# Main_PCB.net
KiCad netlist of a schematic drawn in Altium Designer
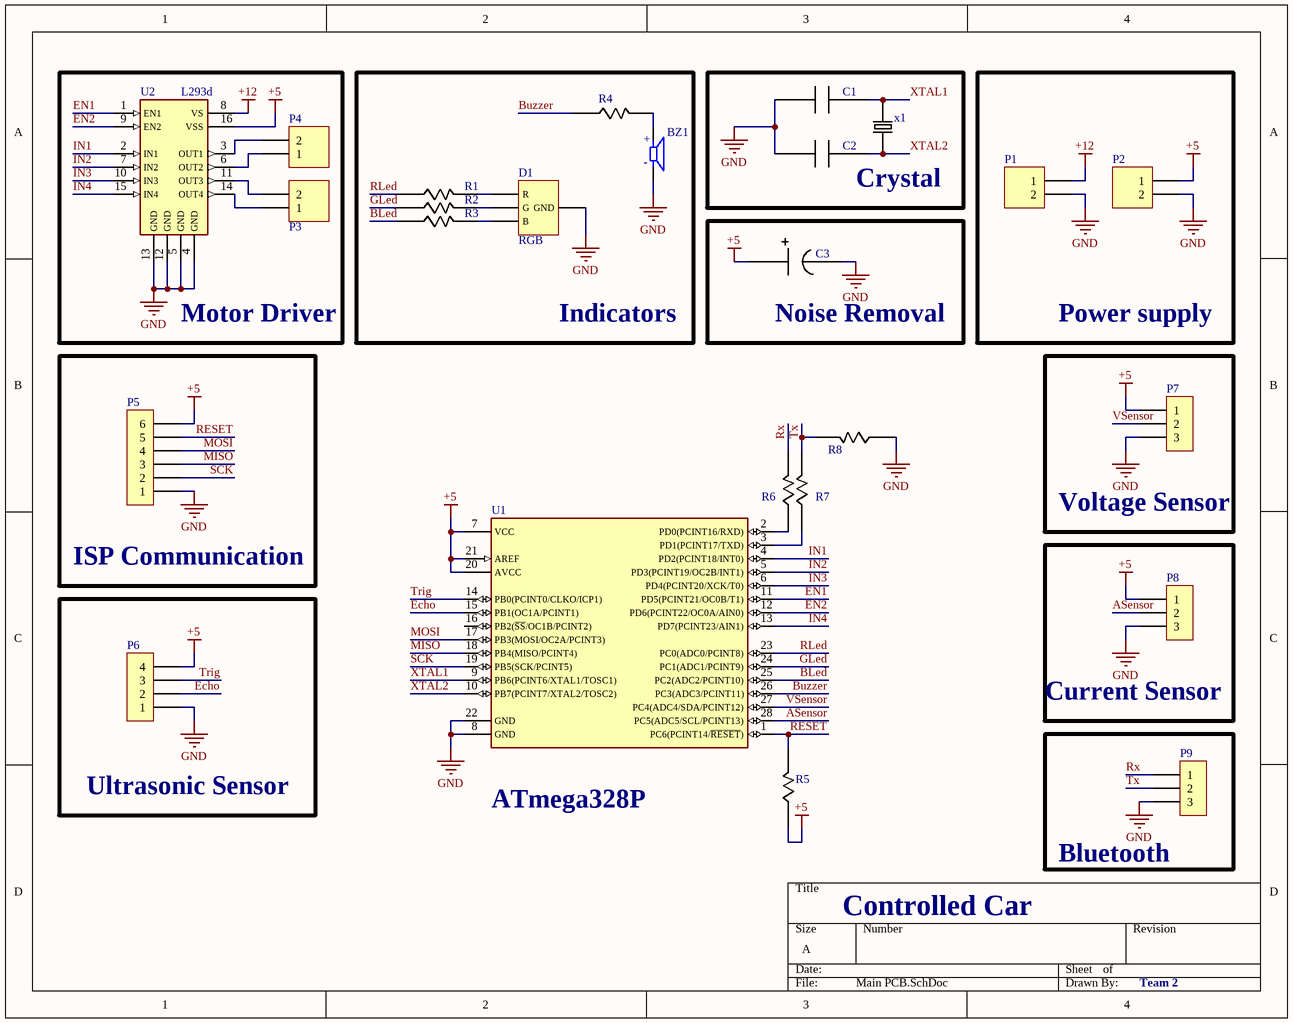
[diagram p0: Main PCB.SchDoc]

(export (version "E")
  (design (tool "Eeschema 10.0.6"))
  (components
    (comp (ref "BZ1") (value "BUZZER") (footprint "BUZZER") (libsource (lib "Schlib1") (part "BUZZER")))
    (comp (ref "C1")
      (value "Capacitor")
      (footprint "CAPACITOR")
      (libsource (lib "Schlib1") (part "Capacitor"))
    )
    (comp (ref "C2")
      (value "Capacitor")
      (footprint "CAPACITOR")
      (libsource (lib "Schlib1") (part "Capacitor"))
    )
    (comp (ref "C3")
      (value "Polarized cap")
      (footprint "POL CAP")
      (libsource (lib "Schlib1") (part "Polarized cap"))
    )
    (comp (ref "D1") (value "RGB") (footprint "RGB") (libsource (lib "Schlib1") (part "RGB")))
    (comp (ref "P1")
      (value "Terminal block")
      (footprint "TERMINAL BLOCK")
      (libsource (lib "Schlib1") (part "Terminal block"))
    )
    (comp (ref "P2")
      (value "Terminal block")
      (footprint "TERMINAL BLOCK")
      (libsource (lib "Schlib1") (part "Terminal block"))
    )
    (comp (ref "P3")
      (value "Terminal block")
      (footprint "TERMINAL BLOCK")
      (libsource (lib "") (part "Terminal block_1"))
    )
    (comp (ref "P4")
      (value "Terminal block")
      (footprint "TERMINAL BLOCK")
      (libsource (lib "") (part "Terminal block_1"))
    )
    (comp (ref "P5")
      (value "6 pins")
      (footprint "6 Pins connector")
      (libsource (lib "Schlib1") (part "6 pins"))
    )
    (comp (ref "P6")
      (value "4 pins")
      (footprint "4 pins connector")
      (libsource (lib "Schlib1") (part "4 pins"))
    )
    (comp (ref "P7")
      (value "3 pins")
      (footprint "3 pins connector")
      (libsource (lib "Schlib1") (part "3 pins"))
    )
    (comp (ref "P8")
      (value "3 pins")
      (footprint "3 pins connector")
      (libsource (lib "Schlib1") (part "3 pins"))
    )
    (comp (ref "P9")
      (value "3 pins")
      (footprint "3 pins connector")
      (libsource (lib "Schlib1") (part "3 pins"))
    )
    (comp (ref "R1") (value "Resistor") (footprint "RESISTOR") (libsource (lib "Schlib1") (part "Resistor")))
    (comp (ref "R2") (value "Resistor") (footprint "RESISTOR") (libsource (lib "Schlib1") (part "Resistor")))
    (comp (ref "R3") (value "Resistor") (footprint "RESISTOR") (libsource (lib "Schlib1") (part "Resistor")))
    (comp (ref "R4") (value "Resistor") (footprint "RESISTOR") (libsource (lib "Schlib1") (part "Resistor")))
    (comp (ref "R5") (value "Resistor") (footprint "RESISTOR") (libsource (lib "Schlib1") (part "Resistor")))
    (comp (ref "R6") (value "Resistor") (footprint "RESISTOR") (libsource (lib "Schlib1") (part "Resistor")))
    (comp (ref "R7") (value "Resistor") (footprint "RESISTOR") (libsource (lib "Schlib1") (part "Resistor")))
    (comp (ref "R8") (value "Resistor") (footprint "RESISTOR") (libsource (lib "Schlib1") (part "Resistor")))
    (comp (ref "U1")
      (value "ATmega328P")
      (footprint "ATmega328P")
      (libsource (lib "Schlib1") (part "ATmega328P"))
    )
    (comp (ref "U2") (value "L293d") (footprint "L293d") (libsource (lib "Schlib1") (part "L293d")))
    (comp (ref "x1") (value "Crystal") (footprint "CRYSTAL") (libsource (lib "Schlib1") (part "Crystal")))
  )
  (nets
    (net (code "1") (name "+5") (class "Default")
      (node (ref "C3") (pin "1") (pinfunction "1_1") (pintype "passive"))
      (node (ref "P2") (pin "1") (pinfunction "1_1") (pintype "passive"))
      (node (ref "P5") (pin "6") (pinfunction "6_6") (pintype "passive"))
      (node (ref "P6") (pin "4") (pinfunction "4_4") (pintype "passive"))
      (node (ref "P7") (pin "1") (pinfunction "1_1") (pintype "passive"))
      (node (ref "P8") (pin "1") (pinfunction "1_1") (pintype "passive"))
      (node (ref "R5") (pin "1") (pinfunction "1_1") (pintype "passive"))
      (node (ref "U1") (pin "20") (pinfunction "AVCC_20") (pintype "power_in"))
      (node (ref "U1") (pin "21") (pinfunction "AREF_21") (pintype "input"))
      (node (ref "U1") (pin "7") (pinfunction "VCC_7") (pintype "power_in"))
      (node (ref "U2") (pin "16") (pinfunction "VSS_16") (pintype "power_in"))
    )
    (net (code "2") (name "+12") (class "Default")
      (node (ref "P1") (pin "1") (pinfunction "1_1") (pintype "passive"))
      (node (ref "U2") (pin "8") (pinfunction "VS_8") (pintype "power_in"))
    )
    (net (code "3") (name "/ASensor") (class "Default")
      (node (ref "P8") (pin "2") (pinfunction "2_2") (pintype "passive"))
      (node (ref "U1") (pin "28") (pinfunction "PC5(ADC5/SCL/PCINT13)_28") (pintype "bidirectional"))
    )
    (net (code "4") (name "/BLed") (class "Default")
      (node (ref "R3") (pin "1") (pinfunction "1_1") (pintype "passive"))
      (node (ref "U1") (pin "25") (pinfunction "PC2(ADC2/PCINT10)_25") (pintype "bidirectional"))
    )
    (net (code "5") (name "/Buzzer") (class "Default")
      (node (ref "R4") (pin "1") (pinfunction "1_1") (pintype "passive"))
      (node (ref "U1") (pin "26") (pinfunction "PC3(ADC3/PCINT11)_26") (pintype "bidirectional"))
    )
    (net (code "6") (name "/EN1") (class "Default")
      (node (ref "U1") (pin "11") (pinfunction "PD5(PCINT21/OC0B/T1)_11") (pintype "bidirectional"))
      (node (ref "U2") (pin "1") (pinfunction "EN1_1") (pintype "input"))
    )
    (net (code "7") (name "/EN2") (class "Default")
      (node (ref "U1") (pin "12") (pinfunction "PD6(PCINT22/OC0A/AIN0)_12") (pintype "bidirectional"))
      (node (ref "U2") (pin "9") (pinfunction "EN2_9") (pintype "input"))
    )
    (net (code "8") (name "/Echo") (class "Default")
      (node (ref "P6") (pin "2") (pinfunction "2_2") (pintype "passive"))
      (node (ref "U1") (pin "15") (pinfunction "PB1(OC1A/PCINT1)_15") (pintype "bidirectional"))
    )
    (net (code "9") (name "/GLed") (class "Default")
      (node (ref "R2") (pin "1") (pinfunction "1_1") (pintype "passive"))
      (node (ref "U1") (pin "24") (pinfunction "PC1(ADC1/PCINT9)_24") (pintype "bidirectional"))
    )
    (net (code "10") (name "/IN1") (class "Default")
      (node (ref "U1") (pin "4") (pinfunction "PD2(PCINT18/INT0)_4") (pintype "bidirectional"))
      (node (ref "U2") (pin "2") (pinfunction "IN1_2") (pintype "input"))
    )
    (net (code "11") (name "/IN2") (class "Default")
      (node (ref "U1") (pin "5") (pinfunction "PD3(PCINT19/OC2B/INT1)_5") (pintype "bidirectional"))
      (node (ref "U2") (pin "7") (pinfunction "IN2_7") (pintype "input"))
    )
    (net (code "12") (name "/IN3") (class "Default")
      (node (ref "U1") (pin "6") (pinfunction "PD4(PCINT20/XCK/T0)_6") (pintype "bidirectional"))
      (node (ref "U2") (pin "10") (pinfunction "IN3_10") (pintype "input"))
    )
    (net (code "13") (name "/IN4") (class "Default")
      (node (ref "U1") (pin "13") (pinfunction "PD7(PCINT23/AIN1)_13") (pintype "bidirectional"))
      (node (ref "U2") (pin "15") (pinfunction "IN4_15") (pintype "input"))
    )
    (net (code "14") (name "/MISO") (class "Default")
      (node (ref "P5") (pin "3") (pinfunction "3_3") (pintype "passive"))
      (node (ref "U1") (pin "18") (pinfunction "PB4(MISO/PCINT4)_18") (pintype "bidirectional"))
    )
    (net (code "15") (name "/MOSI") (class "Default")
      (node (ref "P5") (pin "4") (pinfunction "4_4") (pintype "passive"))
      (node (ref "U1") (pin "17") (pinfunction "PB3(MOSI/OC2A/PCINT3)_17") (pintype "bidirectional"))
    )
    (net (code "16") (name "/RESET") (class "Default")
      (node (ref "P5") (pin "5") (pinfunction "5_5") (pintype "passive"))
      (node (ref "R5") (pin "2") (pinfunction "2_2") (pintype "passive"))
      (node (ref "U1") (pin "1") (pinfunction "PC6(PCINT14/~{RESET})_1") (pintype "bidirectional"))
    )
    (net (code "17") (name "/RLed") (class "Default")
      (node (ref "R1") (pin "1") (pinfunction "1_1") (pintype "passive"))
      (node (ref "U1") (pin "23") (pinfunction "PC0(ADC0/PCINT8)_23") (pintype "bidirectional"))
    )
    (net (code "18") (name "/Rx") (class "Default")
      (node (ref "P9") (pin "1") (pinfunction "1_1") (pintype "passive"))
      (node (ref "R6") (pin "2") (pinfunction "2_2") (pintype "passive"))
    )
    (net (code "19") (name "/SCK") (class "Default")
      (node (ref "P5") (pin "2") (pinfunction "2_2") (pintype "passive"))
      (node (ref "U1") (pin "19") (pinfunction "PB5(SCK/PCINT5)_19") (pintype "bidirectional"))
    )
    (net (code "20") (name "/Trig") (class "Default")
      (node (ref "P6") (pin "3") (pinfunction "3_3") (pintype "passive"))
      (node (ref "U1") (pin "14") (pinfunction "PB0(PCINT0/CLKO/ICP1)_14") (pintype "bidirectional"))
    )
    (net (code "21") (name "/Tx") (class "Default")
      (node (ref "P9") (pin "2") (pinfunction "2_2") (pintype "passive"))
      (node (ref "R7") (pin "2") (pinfunction "2_2") (pintype "passive"))
      (node (ref "R8") (pin "2") (pinfunction "2_2") (pintype "passive"))
    )
    (net (code "22") (name "/VSensor") (class "Default")
      (node (ref "P7") (pin "2") (pinfunction "2_2") (pintype "passive"))
      (node (ref "U1") (pin "27") (pinfunction "PC4(ADC4/SDA/PCINT12)_27") (pintype "bidirectional"))
    )
    (net (code "23") (name "/XTAL1") (class "Default")
      (node (ref "C1") (pin "2") (pinfunction "2_2") (pintype "passive"))
      (node (ref "U1") (pin "9") (pinfunction "PB6(PCINT6/XTAL1/TOSC1)_9") (pintype "bidirectional"))
      (node (ref "x1") (pin "2") (pinfunction "2_2") (pintype "passive"))
    )
    (net (code "24") (name "/XTAL2") (class "Default")
      (node (ref "C2") (pin "2") (pinfunction "2_2") (pintype "passive"))
      (node (ref "U1") (pin "10") (pinfunction "PB7(PCINT7/XTAL2/TOSC2)_10") (pintype "bidirectional"))
      (node (ref "x1") (pin "1") (pinfunction "1_1") (pintype "passive"))
    )
    (net (code "25") (name "GND") (class "Default")
      (node (ref "BZ1") (pin "M") (pinfunction "M_M") (pintype "passive"))
      (node (ref "C1") (pin "1") (pinfunction "1_1") (pintype "passive"))
      (node (ref "C2") (pin "1") (pinfunction "1_1") (pintype "passive"))
      (node (ref "C3") (pin "2") (pinfunction "2_2") (pintype "passive"))
      (node (ref "D1") (pin "2") (pinfunction "GND_2") (pintype "passive"))
      (node (ref "P1") (pin "2") (pinfunction "2_2") (pintype "passive"))
      (node (ref "P2") (pin "2") (pinfunction "2_2") (pintype "passive"))
      (node (ref "P5") (pin "1") (pinfunction "1_1") (pintype "passive"))
      (node (ref "P6") (pin "1") (pinfunction "1_1") (pintype "passive"))
      (node (ref "P7") (pin "3") (pinfunction "3_3") (pintype "passive"))
      (node (ref "P8") (pin "3") (pinfunction "3_3") (pintype "passive"))
      (node (ref "P9") (pin "3") (pinfunction "3_3") (pintype "passive"))
      (node (ref "R8") (pin "1") (pinfunction "1_1") (pintype "passive"))
      (node (ref "U1") (pin "22") (pinfunction "GND_22") (pintype "power_in"))
      (node (ref "U1") (pin "8") (pinfunction "GND_8") (pintype "power_in"))
      (node (ref "U2") (pin "12") (pinfunction "GND_12") (pintype "power_in"))
      (node (ref "U2") (pin "13") (pinfunction "GND_13") (pintype "power_in"))
      (node (ref "U2") (pin "4") (pinfunction "GND_4") (pintype "power_in"))
      (node (ref "U2") (pin "5") (pinfunction "GND_5") (pintype "power_in"))
    )
    (net (code "26") (name "Net-(BZ1-PadP)") (class "Default")
      (node (ref "BZ1") (pin "P") (pinfunction "P_P") (pintype "passive"))
      (node (ref "R4") (pin "2") (pinfunction "2_2") (pintype "passive"))
    )
    (net (code "27") (name "Net-(D1-B)") (class "Default")
      (node (ref "D1") (pin "4") (pinfunction "B_4") (pintype "passive"))
      (node (ref "R3") (pin "2") (pinfunction "2_2") (pintype "passive"))
    )
    (net (code "28") (name "Net-(D1-G)") (class "Default")
      (node (ref "D1") (pin "3") (pinfunction "G_3") (pintype "passive"))
      (node (ref "R2") (pin "2") (pinfunction "2_2") (pintype "passive"))
    )
    (net (code "29") (name "Net-(D1-R)") (class "Default")
      (node (ref "D1") (pin "1") (pinfunction "R_1") (pintype "passive"))
      (node (ref "R1") (pin "2") (pinfunction "2_2") (pintype "passive"))
    )
    (net (code "30") (name "Net-(U1-PD0(PCINT16{slash}RXD))") (class "Default")
      (node (ref "R6") (pin "1") (pinfunction "1_1") (pintype "passive"))
      (node (ref "U1") (pin "2") (pinfunction "PD0(PCINT16/RXD)_2") (pintype "bidirectional"))
    )
    (net (code "31") (name "Net-(U1-PD1(PCINT17{slash}TXD))") (class "Default")
      (node (ref "R7") (pin "1") (pinfunction "1_1") (pintype "passive"))
      (node (ref "U1") (pin "3") (pinfunction "PD1(PCINT17/TXD)_3") (pintype "bidirectional"))
    )
    (net (code "32") (name "Net-(U2-OUT1)") (class "Default")
      (node (ref "P4") (pin "2") (pinfunction "2_2") (pintype "passive"))
      (node (ref "U2") (pin "3") (pinfunction "OUT1_3") (pintype "output"))
    )
    (net (code "33") (name "Net-(U2-OUT2)") (class "Default")
      (node (ref "P4") (pin "1") (pinfunction "1_1") (pintype "passive"))
      (node (ref "U2") (pin "6") (pinfunction "OUT2_6") (pintype "output"))
    )
    (net (code "34") (name "Net-(U2-OUT3)") (class "Default")
      (node (ref "P3") (pin "2") (pinfunction "2_2") (pintype "passive"))
      (node (ref "U2") (pin "11") (pinfunction "OUT3_11") (pintype "output"))
    )
    (net (code "35") (name "Net-(U2-OUT4)") (class "Default")
      (node (ref "P3") (pin "1") (pinfunction "1_1") (pintype "passive"))
      (node (ref "U2") (pin "14") (pinfunction "OUT4_14") (pintype "output"))
    )
    (net (code "36") (name "unconnected-(U1-PB2(~{SS}{slash}OC1B{slash}PCINT2)-Pad16)") (class "Default")
      (node (ref "U1") (pin "16") (pinfunction "PB2(~{SS}/OC1B/PCINT2)_16") (pintype "bidirectional"))
    )
  )
)
